# SFP.net
KiCad netlist of a schematic drawn in Altium Designer
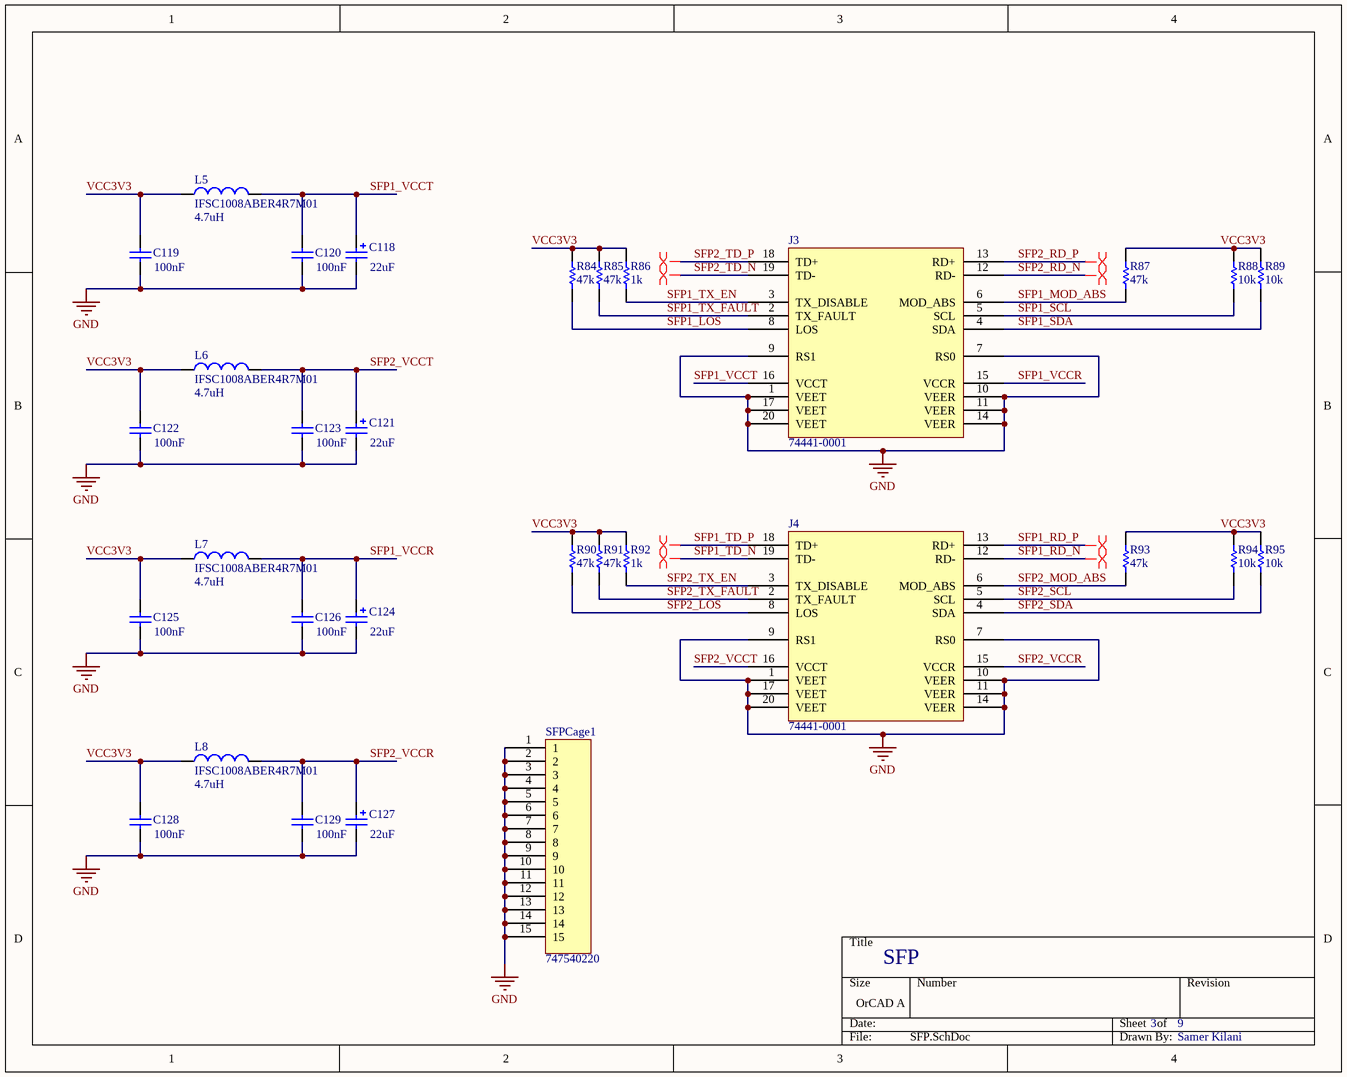
[diagram p0: SFP.SchDoc]

(export (version "E")
  (design (tool "Eeschema 10.0.6"))
  (components
    (comp (ref "C118")
      (value "22uF")
      (footprint "C1206_P")
      (description "Polarized Capacitor (Surface Mount)")
      (fields (field (name "PUBLISHER") "Altium Limited"))
      (libsource (lib "atfclib") (part "Cap Pol"))
    )
    (comp (ref "C119")
      (value "100nF")
      (footprint "C0402")
      (description "Capacitor")
      (fields (field (name "Comment") "Cap") (field (name "PUBLISHER") "Altium Limited"))
      (libsource (lib "atfclib") (part "Cap"))
    )
    (comp (ref "C120")
      (value "100nF")
      (footprint "C0402")
      (description "Capacitor")
      (fields (field (name "Comment") "Cap") (field (name "PUBLISHER") "Altium Limited"))
      (libsource (lib "atfclib") (part "Cap"))
    )
    (comp (ref "C121")
      (value "22uF")
      (footprint "C1206_P")
      (description "Polarized Capacitor (Surface Mount)")
      (fields (field (name "PUBLISHER") "Altium Limited"))
      (libsource (lib "atfclib") (part "Cap Pol"))
    )
    (comp (ref "C122")
      (value "100nF")
      (footprint "C0402")
      (description "Capacitor")
      (fields (field (name "Comment") "Cap") (field (name "PUBLISHER") "Altium Limited"))
      (libsource (lib "atfclib") (part "Cap"))
    )
    (comp (ref "C123")
      (value "100nF")
      (footprint "C0402")
      (description "Capacitor")
      (fields (field (name "Comment") "Cap") (field (name "PUBLISHER") "Altium Limited"))
      (libsource (lib "atfclib") (part "Cap"))
    )
    (comp (ref "C124")
      (value "22uF")
      (footprint "C1206_P")
      (description "Polarized Capacitor (Surface Mount)")
      (fields (field (name "PUBLISHER") "Altium Limited"))
      (libsource (lib "atfclib") (part "Cap Pol"))
    )
    (comp (ref "C125")
      (value "100nF")
      (footprint "C0402")
      (description "Capacitor")
      (fields (field (name "Comment") "Cap") (field (name "PUBLISHER") "Altium Limited"))
      (libsource (lib "atfclib") (part "Cap"))
    )
    (comp (ref "C126")
      (value "100nF")
      (footprint "C0402")
      (description "Capacitor")
      (fields (field (name "Comment") "Cap") (field (name "PUBLISHER") "Altium Limited"))
      (libsource (lib "atfclib") (part "Cap"))
    )
    (comp (ref "C127")
      (value "22uF")
      (footprint "C1206_P")
      (description "Polarized Capacitor (Surface Mount)")
      (fields (field (name "PUBLISHER") "Altium Limited"))
      (libsource (lib "atfclib") (part "Cap Pol"))
    )
    (comp (ref "C128")
      (value "100nF")
      (footprint "C0402")
      (description "Capacitor")
      (fields (field (name "Comment") "Cap") (field (name "PUBLISHER") "Altium Limited"))
      (libsource (lib "atfclib") (part "Cap"))
    )
    (comp (ref "C129")
      (value "100nF")
      (footprint "C0402")
      (description "Capacitor")
      (fields (field (name "Comment") "Cap") (field (name "PUBLISHER") "Altium Limited"))
      (libsource (lib "atfclib") (part "Cap"))
    )
    (comp (ref "J3") (value "74441-0001") (footprint "SFP+20") (libsource (lib "atfclib") (part "SFP+")))
    (comp (ref "J4") (value "74441-0001") (footprint "SFP+20") (libsource (lib "atfclib") (part "SFP+")))
    (comp (ref "L5")
      (value "IFSC1008ABER4R7M01")
      (footprint "IFSC-ER")
      (description "Inductor")
      (fields (field (name "ALTIUM_VALUE") "4.7uH") (field (name "PUBLISHER") "Altium Limited"))
      (libsource (lib "atfclib") (part "Inductor"))
    )
    (comp (ref "L6")
      (value "IFSC1008ABER4R7M01")
      (footprint "IFSC-ER")
      (description "Inductor")
      (fields (field (name "ALTIUM_VALUE") "4.7uH") (field (name "PUBLISHER") "Altium Limited"))
      (libsource (lib "atfclib") (part "Inductor"))
    )
    (comp (ref "L7")
      (value "IFSC1008ABER4R7M01")
      (footprint "IFSC-ER")
      (description "Inductor")
      (fields (field (name "ALTIUM_VALUE") "4.7uH") (field (name "PUBLISHER") "Altium Limited"))
      (libsource (lib "atfclib") (part "Inductor"))
    )
    (comp (ref "L8")
      (value "IFSC1008ABER4R7M01")
      (footprint "IFSC-ER")
      (description "Inductor")
      (fields (field (name "ALTIUM_VALUE") "4.7uH") (field (name "PUBLISHER") "Altium Limited"))
      (libsource (lib "atfclib") (part "Inductor"))
    )
    (comp (ref "R84")
      (value "47k")
      (footprint "R0603")
      (description "Resistor")
      (fields (field (name "Comment") "Res"))
      (libsource (lib "atfclib") (part "Res"))
    )
    (comp (ref "R85")
      (value "47k")
      (footprint "R0603")
      (description "Resistor")
      (fields (field (name "Comment") "Res"))
      (libsource (lib "atfclib") (part "Res"))
    )
    (comp (ref "R86")
      (value "1k")
      (footprint "R0603")
      (description "Resistor")
      (fields (field (name "Comment") "Res"))
      (libsource (lib "atfclib") (part "Res"))
    )
    (comp (ref "R87")
      (value "47k")
      (footprint "R0603")
      (description "Resistor")
      (fields (field (name "Comment") "Res"))
      (libsource (lib "atfclib") (part "Res"))
    )
    (comp (ref "R88")
      (value "10k")
      (footprint "R0603")
      (description "Resistor")
      (fields (field (name "Comment") "Res"))
      (libsource (lib "atfclib") (part "Res"))
    )
    (comp (ref "R89")
      (value "10k")
      (footprint "R0603")
      (description "Resistor")
      (fields (field (name "Comment") "Res"))
      (libsource (lib "atfclib") (part "Res"))
    )
    (comp (ref "R90")
      (value "47k")
      (footprint "R0603")
      (description "Resistor")
      (fields (field (name "Comment") "Res"))
      (libsource (lib "atfclib") (part "Res"))
    )
    (comp (ref "R91")
      (value "47k")
      (footprint "R0603")
      (description "Resistor")
      (fields (field (name "Comment") "Res"))
      (libsource (lib "atfclib") (part "Res"))
    )
    (comp (ref "R92")
      (value "1k")
      (footprint "R0603")
      (description "Resistor")
      (fields (field (name "Comment") "Res"))
      (libsource (lib "atfclib") (part "Res"))
    )
    (comp (ref "R93")
      (value "47k")
      (footprint "R0603")
      (description "Resistor")
      (fields (field (name "Comment") "Res"))
      (libsource (lib "atfclib") (part "Res"))
    )
    (comp (ref "R94")
      (value "10k")
      (footprint "R0603")
      (description "Resistor")
      (fields (field (name "Comment") "Res"))
      (libsource (lib "atfclib") (part "Res"))
    )
    (comp (ref "R95")
      (value "10k")
      (footprint "R0603")
      (description "Resistor")
      (fields (field (name "Comment") "Res"))
      (libsource (lib "atfclib") (part "Res"))
    )
    (comp (ref "SFPCage1")
      (value "747540220")
      (footprint "SFPcage - dual")
      (libsource (lib "atfclib") (part "SFPcagedual"))
    )
  )
  (nets
    (net (code "1") (name "/SFP1_LOS") (class "Default")
      (node (ref "J3") (pin "8") (pinfunction "LOS_8") (pintype "passive"))
      (node (ref "R84") (pin "2") (pinfunction "2_2") (pintype "passive"))
    )
    (net (code "2") (name "/SFP1_MOD_ABS") (class "Default")
      (node (ref "J3") (pin "6") (pinfunction "MOD_ABS_6") (pintype "passive"))
      (node (ref "R87") (pin "2") (pinfunction "2_2") (pintype "passive"))
    )
    (net (code "3") (name "/SFP1_RD_N") (class "Default")
      (node (ref "J4") (pin "12") (pinfunction "RD-_12") (pintype "passive"))
    )
    (net (code "4") (name "/SFP1_RD_P") (class "Default")
      (node (ref "J4") (pin "13") (pinfunction "RD+_13") (pintype "passive"))
    )
    (net (code "5") (name "/SFP1_SCL") (class "Default")
      (node (ref "J3") (pin "5") (pinfunction "SCL_5") (pintype "passive"))
      (node (ref "R88") (pin "2") (pinfunction "2_2") (pintype "passive"))
    )
    (net (code "6") (name "/SFP1_SDA") (class "Default")
      (node (ref "J3") (pin "4") (pinfunction "SDA_4") (pintype "passive"))
      (node (ref "R89") (pin "2") (pinfunction "2_2") (pintype "passive"))
    )
    (net (code "7") (name "/SFP1_TD_N") (class "Default")
      (node (ref "J4") (pin "19") (pinfunction "TD-_19") (pintype "passive"))
    )
    (net (code "8") (name "/SFP1_TD_P") (class "Default")
      (node (ref "J4") (pin "18") (pinfunction "TD+_18") (pintype "passive"))
    )
    (net (code "9") (name "/SFP1_TX_EN") (class "Default")
      (node (ref "J3") (pin "3") (pinfunction "TX_DISABLE_3") (pintype "passive"))
      (node (ref "R86") (pin "2") (pinfunction "2_2") (pintype "passive"))
    )
    (net (code "10") (name "/SFP1_TX_FAULT") (class "Default")
      (node (ref "J3") (pin "2") (pinfunction "TX_FAULT_2") (pintype "passive"))
      (node (ref "R85") (pin "2") (pinfunction "2_2") (pintype "passive"))
    )
    (net (code "11") (name "/SFP1_VCCR") (class "Default")
      (node (ref "C124") (pin "1") (pinfunction "1_1") (pintype "passive"))
      (node (ref "C126") (pin "2") (pinfunction "2_2") (pintype "passive"))
      (node (ref "J3") (pin "15") (pinfunction "VCCR_15") (pintype "passive"))
      (node (ref "L7") (pin "2") (pinfunction "2_2") (pintype "passive"))
    )
    (net (code "12") (name "/SFP1_VCCT") (class "Default")
      (node (ref "C118") (pin "1") (pinfunction "1_1") (pintype "passive"))
      (node (ref "C120") (pin "2") (pinfunction "2_2") (pintype "passive"))
      (node (ref "J3") (pin "16") (pinfunction "VCCT_16") (pintype "passive"))
      (node (ref "L5") (pin "2") (pinfunction "2_2") (pintype "passive"))
    )
    (net (code "13") (name "/SFP2_LOS") (class "Default")
      (node (ref "J4") (pin "8") (pinfunction "LOS_8") (pintype "passive"))
      (node (ref "R90") (pin "2") (pinfunction "2_2") (pintype "passive"))
    )
    (net (code "14") (name "/SFP2_MOD_ABS") (class "Default")
      (node (ref "J4") (pin "6") (pinfunction "MOD_ABS_6") (pintype "passive"))
      (node (ref "R93") (pin "2") (pinfunction "2_2") (pintype "passive"))
    )
    (net (code "15") (name "/SFP2_RD_N") (class "Default")
      (node (ref "J3") (pin "12") (pinfunction "RD-_12") (pintype "passive"))
    )
    (net (code "16") (name "/SFP2_RD_P") (class "Default")
      (node (ref "J3") (pin "13") (pinfunction "RD+_13") (pintype "passive"))
    )
    (net (code "17") (name "/SFP2_SCL") (class "Default")
      (node (ref "J4") (pin "5") (pinfunction "SCL_5") (pintype "passive"))
      (node (ref "R94") (pin "2") (pinfunction "2_2") (pintype "passive"))
    )
    (net (code "18") (name "/SFP2_SDA") (class "Default")
      (node (ref "J4") (pin "4") (pinfunction "SDA_4") (pintype "passive"))
      (node (ref "R95") (pin "2") (pinfunction "2_2") (pintype "passive"))
    )
    (net (code "19") (name "/SFP2_TD_N") (class "Default")
      (node (ref "J3") (pin "19") (pinfunction "TD-_19") (pintype "passive"))
    )
    (net (code "20") (name "/SFP2_TD_P") (class "Default")
      (node (ref "J3") (pin "18") (pinfunction "TD+_18") (pintype "passive"))
    )
    (net (code "21") (name "/SFP2_TX_EN") (class "Default")
      (node (ref "J4") (pin "3") (pinfunction "TX_DISABLE_3") (pintype "passive"))
      (node (ref "R92") (pin "2") (pinfunction "2_2") (pintype "passive"))
    )
    (net (code "22") (name "/SFP2_TX_FAULT") (class "Default")
      (node (ref "J4") (pin "2") (pinfunction "TX_FAULT_2") (pintype "passive"))
      (node (ref "R91") (pin "2") (pinfunction "2_2") (pintype "passive"))
    )
    (net (code "23") (name "/SFP2_VCCR") (class "Default")
      (node (ref "C127") (pin "1") (pinfunction "1_1") (pintype "passive"))
      (node (ref "C129") (pin "2") (pinfunction "2_2") (pintype "passive"))
      (node (ref "J4") (pin "15") (pinfunction "VCCR_15") (pintype "passive"))
      (node (ref "L8") (pin "2") (pinfunction "2_2") (pintype "passive"))
    )
    (net (code "24") (name "/SFP2_VCCT") (class "Default")
      (node (ref "C121") (pin "1") (pinfunction "1_1") (pintype "passive"))
      (node (ref "C123") (pin "2") (pinfunction "2_2") (pintype "passive"))
      (node (ref "J4") (pin "16") (pinfunction "VCCT_16") (pintype "passive"))
      (node (ref "L6") (pin "2") (pinfunction "2_2") (pintype "passive"))
    )
    (net (code "25") (name "/VCC3V3") (class "Default")
      (node (ref "C119") (pin "2") (pinfunction "2_2") (pintype "passive"))
      (node (ref "C122") (pin "2") (pinfunction "2_2") (pintype "passive"))
      (node (ref "C125") (pin "2") (pinfunction "2_2") (pintype "passive"))
      (node (ref "C128") (pin "2") (pinfunction "2_2") (pintype "passive"))
      (node (ref "L5") (pin "1") (pinfunction "1_1") (pintype "passive"))
      (node (ref "L6") (pin "1") (pinfunction "1_1") (pintype "passive"))
      (node (ref "L7") (pin "1") (pinfunction "1_1") (pintype "passive"))
      (node (ref "L8") (pin "1") (pinfunction "1_1") (pintype "passive"))
      (node (ref "R84") (pin "1") (pinfunction "1_1") (pintype "passive"))
      (node (ref "R85") (pin "1") (pinfunction "1_1") (pintype "passive"))
      (node (ref "R86") (pin "1") (pinfunction "1_1") (pintype "passive"))
      (node (ref "R87") (pin "1") (pinfunction "1_1") (pintype "passive"))
      (node (ref "R88") (pin "1") (pinfunction "1_1") (pintype "passive"))
      (node (ref "R89") (pin "1") (pinfunction "1_1") (pintype "passive"))
      (node (ref "R90") (pin "1") (pinfunction "1_1") (pintype "passive"))
      (node (ref "R91") (pin "1") (pinfunction "1_1") (pintype "passive"))
      (node (ref "R92") (pin "1") (pinfunction "1_1") (pintype "passive"))
      (node (ref "R93") (pin "1") (pinfunction "1_1") (pintype "passive"))
      (node (ref "R94") (pin "1") (pinfunction "1_1") (pintype "passive"))
      (node (ref "R95") (pin "1") (pinfunction "1_1") (pintype "passive"))
    )
    (net (code "26") (name "GND") (class "Default")
      (node (ref "C118") (pin "2") (pinfunction "2_2") (pintype "passive"))
      (node (ref "C119") (pin "1") (pinfunction "1_1") (pintype "passive"))
      (node (ref "C120") (pin "1") (pinfunction "1_1") (pintype "passive"))
      (node (ref "C121") (pin "2") (pinfunction "2_2") (pintype "passive"))
      (node (ref "C122") (pin "1") (pinfunction "1_1") (pintype "passive"))
      (node (ref "C123") (pin "1") (pinfunction "1_1") (pintype "passive"))
      (node (ref "C124") (pin "2") (pinfunction "2_2") (pintype "passive"))
      (node (ref "C125") (pin "1") (pinfunction "1_1") (pintype "passive"))
      (node (ref "C126") (pin "1") (pinfunction "1_1") (pintype "passive"))
      (node (ref "C127") (pin "2") (pinfunction "2_2") (pintype "passive"))
      (node (ref "C128") (pin "1") (pinfunction "1_1") (pintype "passive"))
      (node (ref "C129") (pin "1") (pinfunction "1_1") (pintype "passive"))
      (node (ref "J3") (pin "1") (pinfunction "VEET_1") (pintype "passive"))
      (node (ref "J3") (pin "10") (pinfunction "VEER_10") (pintype "passive"))
      (node (ref "J3") (pin "11") (pinfunction "VEER_11") (pintype "passive"))
      (node (ref "J3") (pin "14") (pinfunction "VEER_14") (pintype "passive"))
      (node (ref "J3") (pin "17") (pinfunction "VEET_17") (pintype "passive"))
      (node (ref "J3") (pin "20") (pinfunction "VEET_20") (pintype "passive"))
      (node (ref "J3") (pin "7") (pinfunction "RS0_7") (pintype "passive"))
      (node (ref "J3") (pin "9") (pinfunction "RS1_9") (pintype "passive"))
      (node (ref "J4") (pin "1") (pinfunction "VEET_1") (pintype "passive"))
      (node (ref "J4") (pin "10") (pinfunction "VEER_10") (pintype "passive"))
      (node (ref "J4") (pin "11") (pinfunction "VEER_11") (pintype "passive"))
      (node (ref "J4") (pin "14") (pinfunction "VEER_14") (pintype "passive"))
      (node (ref "J4") (pin "17") (pinfunction "VEET_17") (pintype "passive"))
      (node (ref "J4") (pin "20") (pinfunction "VEET_20") (pintype "passive"))
      (node (ref "J4") (pin "7") (pinfunction "RS0_7") (pintype "passive"))
      (node (ref "J4") (pin "9") (pinfunction "RS1_9") (pintype "passive"))
      (node (ref "SFPCage1") (pin "1") (pinfunction "1_1") (pintype "passive"))
      (node (ref "SFPCage1") (pin "10") (pinfunction "10_10") (pintype "passive"))
      (node (ref "SFPCage1") (pin "11") (pinfunction "11_11") (pintype "passive"))
      (node (ref "SFPCage1") (pin "12") (pinfunction "12_12") (pintype "passive"))
      (node (ref "SFPCage1") (pin "13") (pinfunction "13_13") (pintype "passive"))
      (node (ref "SFPCage1") (pin "14") (pinfunction "14_14") (pintype "passive"))
      (node (ref "SFPCage1") (pin "15") (pinfunction "15_15") (pintype "passive"))
      (node (ref "SFPCage1") (pin "2") (pinfunction "2_2") (pintype "passive"))
      (node (ref "SFPCage1") (pin "3") (pinfunction "3_3") (pintype "passive"))
      (node (ref "SFPCage1") (pin "4") (pinfunction "4_4") (pintype "passive"))
      (node (ref "SFPCage1") (pin "5") (pinfunction "5_5") (pintype "passive"))
      (node (ref "SFPCage1") (pin "6") (pinfunction "6_6") (pintype "passive"))
      (node (ref "SFPCage1") (pin "7") (pinfunction "7_7") (pintype "passive"))
      (node (ref "SFPCage1") (pin "8") (pinfunction "8_8") (pintype "passive"))
      (node (ref "SFPCage1") (pin "9") (pinfunction "9_9") (pintype "passive"))
    )
  )
)
